# AUDIO_PR_2020.net
KiCad netlist of a schematic drawn in EAGLE
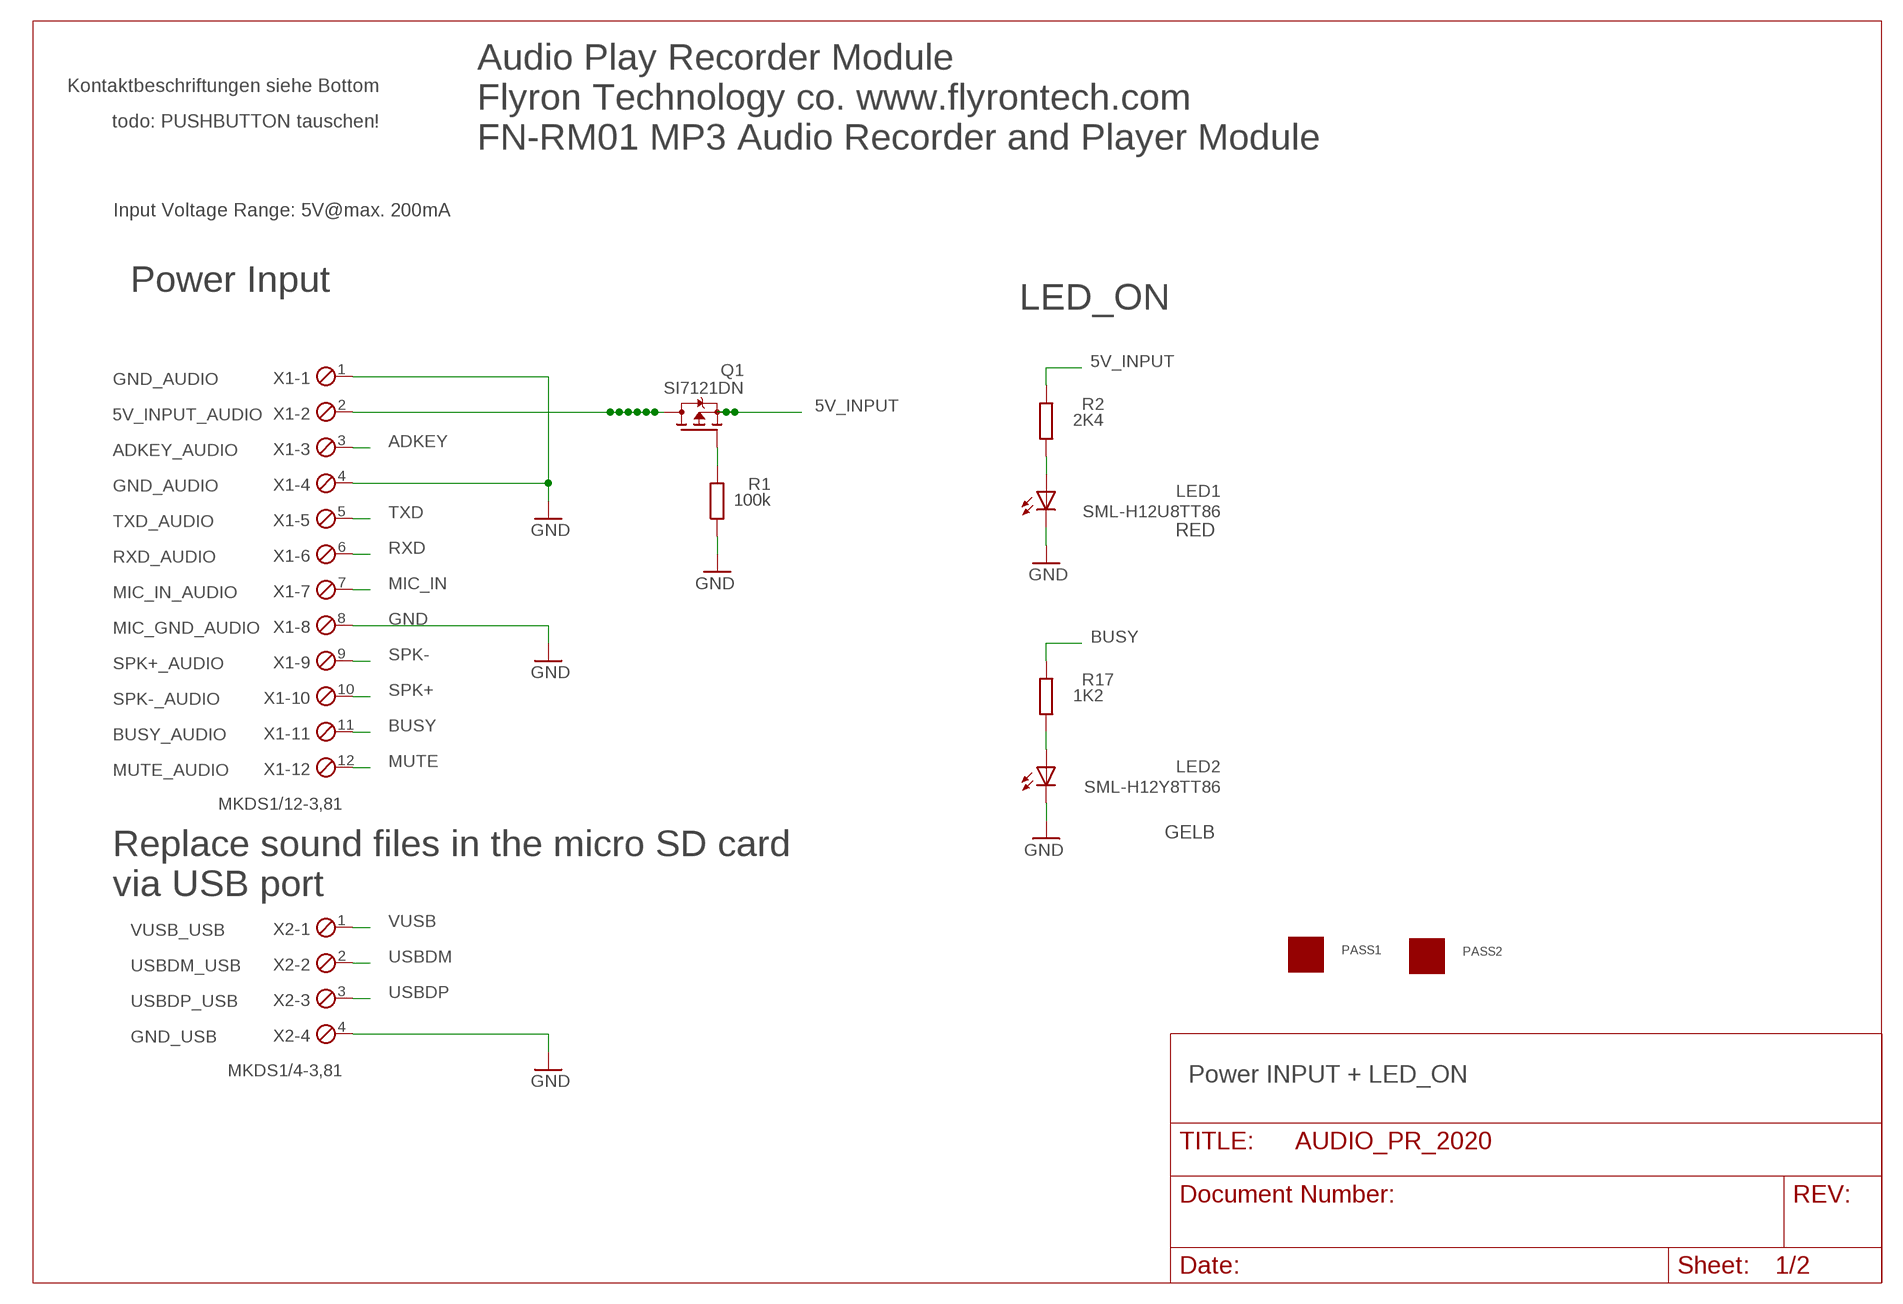
[diagram p0: schematic, sheet 1]
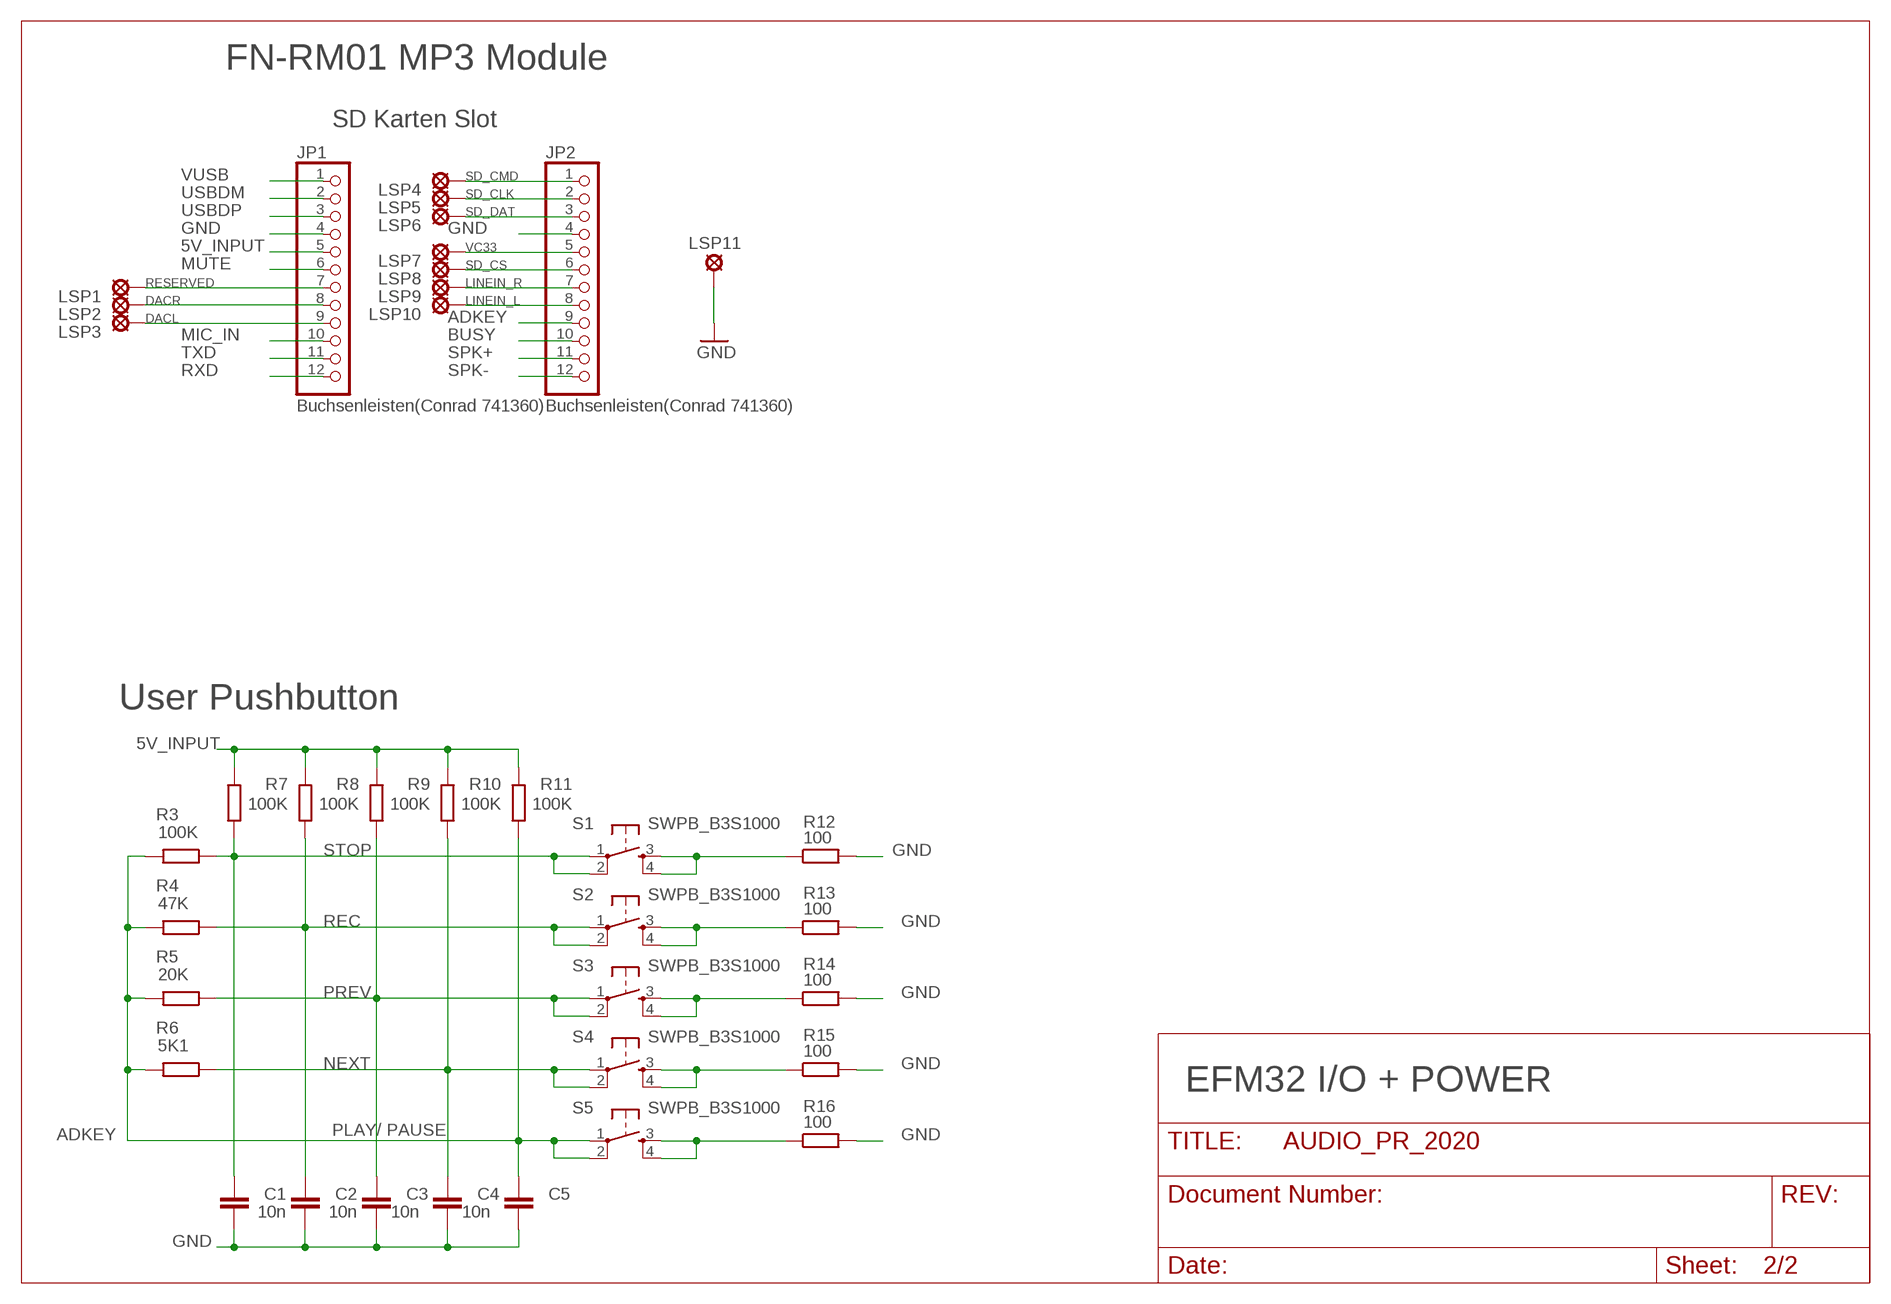
[diagram p1: schematic, sheet 2]

(export (version "E")
  (design (tool "Eeschema 10.0.6"))
  (components
    (comp (ref "LED1")
      (value "SML-H12U8TT86")
      (footprint "eagle-import:CHIPLED_0805")
      (libsource (lib "eagle-import") (part "LEDCHIPLED_0805"))
    )
    (comp (ref "LED2")
      (value "SML-H12Y8TT86")
      (footprint "eagle-import:CHIPLED_0805")
      (libsource (lib "eagle-import") (part "LEDCHIPLED_0805"))
    )
    (comp (ref "PASS1")
      (value "ROUND_1MM1.5")
      (footprint "eagle-import:ROUND2_1.5MM")
      (libsource (lib "eagle-import") (part "ROUND_1MM1.5"))
    )
    (comp (ref "PASS2")
      (value "ROUND_1MM1.5")
      (footprint "eagle-import:ROUND2_1.5MM")
      (libsource (lib "eagle-import") (part "ROUND_1MM1.5"))
    )
    (comp (ref "Q1")
      (value "SI7121DN")
      (footprint "eagle-import:TRANSISTOR-FET_1212-8S")
      (libsource (lib "eagle-import") (part "TRANSISTOR-FET_SI7113DN"))
    )
    (comp (ref "R1")
      (value "100k")
      (footprint "eagle-import:R0805")
      (libsource (lib "eagle-import") (part "R-EU_R0805"))
    )
    (comp (ref "R2")
      (value "2K4")
      (footprint "eagle-import:R0805")
      (libsource (lib "eagle-import") (part "R-EU_R0805"))
    )
    (comp (ref "R17")
      (value "1K2")
      (footprint "eagle-import:R0805")
      (libsource (lib "eagle-import") (part "R-EU_R0805"))
    )
    (comp (ref "X1")
      (value "MKDS1/12-3,81")
      (footprint "eagle-import:12POL381")
      (libsource (lib "eagle-import") (part "MKDS1/12-3,81"))
    )
    (comp (ref "X2")
      (value "MKDS1/4-3,81")
      (footprint "eagle-import:4POL381")
      (libsource (lib "eagle-import") (part "MKDS1/4-3,81"))
    )
    (comp (ref "C1")
      (value "10n")
      (footprint "eagle-import:C0603")
      (libsource (lib "eagle-import") (part "C-EUC0603"))
    )
    (comp (ref "C2")
      (value "10n")
      (footprint "eagle-import:C0603")
      (libsource (lib "eagle-import") (part "C-EUC0603"))
    )
    (comp (ref "C3")
      (value "10n")
      (footprint "eagle-import:C0603")
      (libsource (lib "eagle-import") (part "C-EUC0603"))
    )
    (comp (ref "C4")
      (value "10n")
      (footprint "eagle-import:C0603")
      (libsource (lib "eagle-import") (part "C-EUC0603"))
    )
    (comp (ref "C5")
      (value "10n")
      (footprint "eagle-import:C0603")
      (libsource (lib "eagle-import") (part "C-EUC0603"))
    )
    (comp (ref "JP1")
      (value "Buchsenleisten(Conrad 741360)")
      (footprint "eagle-import:1X12")
      (libsource (lib "eagle-import") (part "PINHD-1X12"))
    )
    (comp (ref "JP2")
      (value "Buchsenleisten(Conrad 741360)")
      (footprint "eagle-import:1X12")
      (libsource (lib "eagle-import") (part "PINHD-1X12"))
    )
    (comp (ref "LSP1")
      (value "LSP10")
      (footprint "eagle-import:LSP10")
      (libsource (lib "eagle-import") (part "LSP10"))
    )
    (comp (ref "LSP2")
      (value "LSP10")
      (footprint "eagle-import:LSP10")
      (libsource (lib "eagle-import") (part "LSP10"))
    )
    (comp (ref "LSP3")
      (value "LSP10")
      (footprint "eagle-import:LSP10")
      (libsource (lib "eagle-import") (part "LSP10"))
    )
    (comp (ref "LSP4")
      (value "LSP10")
      (footprint "eagle-import:LSP10")
      (libsource (lib "eagle-import") (part "LSP10"))
    )
    (comp (ref "LSP5")
      (value "LSP10")
      (footprint "eagle-import:LSP10")
      (libsource (lib "eagle-import") (part "LSP10"))
    )
    (comp (ref "LSP6")
      (value "LSP10")
      (footprint "eagle-import:LSP10")
      (libsource (lib "eagle-import") (part "LSP10"))
    )
    (comp (ref "LSP7")
      (value "LSP10")
      (footprint "eagle-import:LSP10")
      (libsource (lib "eagle-import") (part "LSP10"))
    )
    (comp (ref "LSP8")
      (value "LSP10")
      (footprint "eagle-import:LSP10")
      (libsource (lib "eagle-import") (part "LSP10"))
    )
    (comp (ref "LSP9")
      (value "LSP10")
      (footprint "eagle-import:LSP10")
      (libsource (lib "eagle-import") (part "LSP10"))
    )
    (comp (ref "LSP10")
      (value "LSP10")
      (footprint "eagle-import:LSP10")
      (libsource (lib "eagle-import") (part "LSP10"))
    )
    (comp (ref "LSP11")
      (value "LSP10")
      (footprint "eagle-import:LSP10")
      (libsource (lib "eagle-import") (part "LSP10"))
    )
    (comp (ref "R3")
      (value "100K")
      (footprint "eagle-import:R0805")
      (libsource (lib "eagle-import") (part "R-EU_R0805"))
    )
    (comp (ref "R4")
      (value "47K")
      (footprint "eagle-import:R0805")
      (libsource (lib "eagle-import") (part "R-EU_R0805"))
    )
    (comp (ref "R5")
      (value "20K")
      (footprint "eagle-import:R0805")
      (libsource (lib "eagle-import") (part "R-EU_R0805"))
    )
    (comp (ref "R6")
      (value "5K1")
      (footprint "eagle-import:R0805")
      (libsource (lib "eagle-import") (part "R-EU_R0805"))
    )
    (comp (ref "R7")
      (value "100K")
      (footprint "eagle-import:R0805")
      (libsource (lib "eagle-import") (part "R-EU_R0805"))
    )
    (comp (ref "R8")
      (value "100K")
      (footprint "eagle-import:R0805")
      (libsource (lib "eagle-import") (part "R-EU_R0805"))
    )
    (comp (ref "R9")
      (value "100K")
      (footprint "eagle-import:R0805")
      (libsource (lib "eagle-import") (part "R-EU_R0805"))
    )
    (comp (ref "R10")
      (value "100K")
      (footprint "eagle-import:R0805")
      (libsource (lib "eagle-import") (part "R-EU_R0805"))
    )
    (comp (ref "R11")
      (value "100K")
      (footprint "eagle-import:R0805")
      (libsource (lib "eagle-import") (part "R-EU_R0805"))
    )
    (comp (ref "R12")
      (value "100")
      (footprint "eagle-import:R0805")
      (libsource (lib "eagle-import") (part "R-EU_R0805"))
    )
    (comp (ref "R13")
      (value "100")
      (footprint "eagle-import:R0805")
      (libsource (lib "eagle-import") (part "R-EU_R0805"))
    )
    (comp (ref "R14")
      (value "100")
      (footprint "eagle-import:R0805")
      (libsource (lib "eagle-import") (part "R-EU_R0805"))
    )
    (comp (ref "R15")
      (value "100")
      (footprint "eagle-import:R0805")
      (libsource (lib "eagle-import") (part "R-EU_R0805"))
    )
    (comp (ref "R16")
      (value "100")
      (footprint "eagle-import:R0805")
      (libsource (lib "eagle-import") (part "R-EU_R0805"))
    )
    (comp (ref "S1")
      (value "SWPB_B3S1000")
      (footprint "eagle-import:DTSM-6")
      (libsource (lib "eagle-import") (part "DTSM-6"))
    )
    (comp (ref "S2")
      (value "SWPB_B3S1000")
      (footprint "eagle-import:DTSM-6")
      (libsource (lib "eagle-import") (part "DTSM-6"))
    )
    (comp (ref "S3")
      (value "SWPB_B3S1000")
      (footprint "eagle-import:DTSM-6")
      (libsource (lib "eagle-import") (part "DTSM-6"))
    )
    (comp (ref "S4")
      (value "SWPB_B3S1000")
      (footprint "eagle-import:DTSM-6")
      (libsource (lib "eagle-import") (part "DTSM-6"))
    )
    (comp (ref "S5")
      (value "SWPB_B3S1000")
      (footprint "eagle-import:DTSM-6")
      (libsource (lib "eagle-import") (part "DTSM-6"))
    )
  )
  (nets
    (net (code "1") (name "5V_INPUT") (class "Default")
      (node (ref "JP1") (pin "5") (pinfunction "5_5") (pintype "passive"))
      (node (ref "Q1") (pin "1") (pinfunction "S_1") (pintype "passive"))
      (node (ref "Q1") (pin "2") (pinfunction "S_2") (pintype "passive"))
      (node (ref "Q1") (pin "3") (pinfunction "S_3") (pintype "passive"))
      (node (ref "R10") (pin "2") (pinfunction "2_2") (pintype "passive"))
      (node (ref "R11") (pin "2") (pinfunction "2_2") (pintype "passive"))
      (node (ref "R2") (pin "1") (pinfunction "1_1") (pintype "passive"))
      (node (ref "R7") (pin "2") (pinfunction "2_2") (pintype "passive"))
      (node (ref "R8") (pin "2") (pinfunction "2_2") (pintype "passive"))
      (node (ref "R9") (pin "2") (pinfunction "2_2") (pintype "passive"))
    )
    (net (code "2") (name "ADKEY") (class "Default")
      (node (ref "C5") (pin "2") (pinfunction "2_2") (pintype "passive"))
      (node (ref "JP2") (pin "9") (pinfunction "9_9") (pintype "passive"))
      (node (ref "R11") (pin "1") (pinfunction "1_1") (pintype "passive"))
      (node (ref "R3") (pin "2") (pinfunction "2_2") (pintype "passive"))
      (node (ref "R4") (pin "2") (pinfunction "2_2") (pintype "passive"))
      (node (ref "R5") (pin "2") (pinfunction "2_2") (pintype "passive"))
      (node (ref "R6") (pin "2") (pinfunction "2_2") (pintype "passive"))
      (node (ref "S5") (pin "1") (pinfunction "1_1") (pintype "passive"))
      (node (ref "S5") (pin "2") (pinfunction "2_2") (pintype "passive"))
      (node (ref "X1") (pin "3") (pinfunction "1_3") (pintype "passive"))
    )
    (net (code "3") (name "BUSY") (class "Default")
      (node (ref "JP2") (pin "10") (pinfunction "10_10") (pintype "passive"))
      (node (ref "R17") (pin "1") (pinfunction "1_1") (pintype "passive"))
      (node (ref "X1") (pin "11") (pinfunction "1_11") (pintype "passive"))
    )
    (net (code "4") (name "DACL") (class "Default")
      (node (ref "JP1") (pin "9") (pinfunction "9_9") (pintype "passive"))
      (node (ref "LSP3") (pin "MP") (pinfunction "MP_MP") (pintype "passive"))
    )
    (net (code "5") (name "DACR") (class "Default")
      (node (ref "JP1") (pin "8") (pinfunction "8_8") (pintype "passive"))
      (node (ref "LSP2") (pin "MP") (pinfunction "MP_MP") (pintype "passive"))
    )
    (net (code "6") (name "GND") (class "Default")
      (node (ref "C1") (pin "1") (pinfunction "1_1") (pintype "passive"))
      (node (ref "C2") (pin "1") (pinfunction "1_1") (pintype "passive"))
      (node (ref "C3") (pin "1") (pinfunction "1_1") (pintype "passive"))
      (node (ref "C4") (pin "1") (pinfunction "1_1") (pintype "passive"))
      (node (ref "C5") (pin "1") (pinfunction "1_1") (pintype "passive"))
      (node (ref "JP1") (pin "4") (pinfunction "4_4") (pintype "passive"))
      (node (ref "JP2") (pin "4") (pinfunction "4_4") (pintype "passive"))
      (node (ref "LED1") (pin "C") (pinfunction "C_C") (pintype "passive"))
      (node (ref "LED2") (pin "C") (pinfunction "C_C") (pintype "passive"))
      (node (ref "LSP11") (pin "MP") (pinfunction "MP_MP") (pintype "passive"))
      (node (ref "R1") (pin "1") (pinfunction "1_1") (pintype "passive"))
      (node (ref "R12") (pin "2") (pinfunction "2_2") (pintype "passive"))
      (node (ref "R13") (pin "2") (pinfunction "2_2") (pintype "passive"))
      (node (ref "R14") (pin "2") (pinfunction "2_2") (pintype "passive"))
      (node (ref "R15") (pin "2") (pinfunction "2_2") (pintype "passive"))
      (node (ref "R16") (pin "2") (pinfunction "2_2") (pintype "passive"))
      (node (ref "X1") (pin "1") (pinfunction "1_1") (pintype "passive"))
      (node (ref "X1") (pin "4") (pinfunction "1_4") (pintype "passive"))
      (node (ref "X1") (pin "8") (pinfunction "1_8") (pintype "passive"))
      (node (ref "X2") (pin "4") (pinfunction "1_4") (pintype "passive"))
    )
    (net (code "7") (name "LINEIN_L") (class "Default")
      (node (ref "JP2") (pin "8") (pinfunction "8_8") (pintype "passive"))
      (node (ref "LSP10") (pin "MP") (pinfunction "MP_MP") (pintype "passive"))
    )
    (net (code "8") (name "LINEIN_R") (class "Default")
      (node (ref "JP2") (pin "7") (pinfunction "7_7") (pintype "passive"))
      (node (ref "LSP9") (pin "MP") (pinfunction "MP_MP") (pintype "passive"))
    )
    (net (code "9") (name "MIC_IN") (class "Default")
      (node (ref "JP1") (pin "10") (pinfunction "10_10") (pintype "passive"))
      (node (ref "X1") (pin "7") (pinfunction "1_7") (pintype "passive"))
    )
    (net (code "10") (name "MUTE") (class "Default")
      (node (ref "JP1") (pin "6") (pinfunction "6_6") (pintype "passive"))
      (node (ref "X1") (pin "12") (pinfunction "1_12") (pintype "passive"))
    )
    (net (code "11") (name "NEXT") (class "Default")
      (node (ref "C4") (pin "2") (pinfunction "2_2") (pintype "passive"))
      (node (ref "R10") (pin "1") (pinfunction "1_1") (pintype "passive"))
      (node (ref "R6") (pin "1") (pinfunction "1_1") (pintype "passive"))
      (node (ref "S4") (pin "1") (pinfunction "1_1") (pintype "passive"))
      (node (ref "S4") (pin "2") (pinfunction "2_2") (pintype "passive"))
    )
    (net (code "12") (name "Net-(LED1-PadA)") (class "Default")
      (node (ref "LED1") (pin "A") (pinfunction "A_A") (pintype "passive"))
      (node (ref "R2") (pin "2") (pinfunction "2_2") (pintype "passive"))
    )
    (net (code "13") (name "Net-(LED2-PadA)") (class "Default")
      (node (ref "LED2") (pin "A") (pinfunction "A_A") (pintype "passive"))
      (node (ref "R17") (pin "2") (pinfunction "2_2") (pintype "passive"))
    )
    (net (code "14") (name "Net-(Q1-G)") (class "Default")
      (node (ref "Q1") (pin "4") (pinfunction "G_4") (pintype "passive"))
      (node (ref "R1") (pin "2") (pinfunction "2_2") (pintype "passive"))
    )
    (net (code "15") (name "Net-(R12-Pad1)") (class "Default")
      (node (ref "R12") (pin "1") (pinfunction "1_1") (pintype "passive"))
      (node (ref "S1") (pin "3") (pinfunction "3_3") (pintype "passive"))
      (node (ref "S1") (pin "4") (pinfunction "4_4") (pintype "passive"))
    )
    (net (code "16") (name "Net-(R13-Pad1)") (class "Default")
      (node (ref "R13") (pin "1") (pinfunction "1_1") (pintype "passive"))
      (node (ref "S2") (pin "3") (pinfunction "3_3") (pintype "passive"))
      (node (ref "S2") (pin "4") (pinfunction "4_4") (pintype "passive"))
    )
    (net (code "17") (name "Net-(R14-Pad1)") (class "Default")
      (node (ref "R14") (pin "1") (pinfunction "1_1") (pintype "passive"))
      (node (ref "S3") (pin "3") (pinfunction "3_3") (pintype "passive"))
      (node (ref "S3") (pin "4") (pinfunction "4_4") (pintype "passive"))
    )
    (net (code "18") (name "Net-(R15-Pad1)") (class "Default")
      (node (ref "R15") (pin "1") (pinfunction "1_1") (pintype "passive"))
      (node (ref "S4") (pin "3") (pinfunction "3_3") (pintype "passive"))
      (node (ref "S4") (pin "4") (pinfunction "4_4") (pintype "passive"))
    )
    (net (code "19") (name "Net-(R16-Pad1)") (class "Default")
      (node (ref "R16") (pin "1") (pinfunction "1_1") (pintype "passive"))
      (node (ref "S5") (pin "3") (pinfunction "3_3") (pintype "passive"))
      (node (ref "S5") (pin "4") (pinfunction "4_4") (pintype "passive"))
    )
    (net (code "20") (name "Net-(X1E-1)") (class "Default")
      (node (ref "Q1") (pin "10") (pinfunction "D_10") (pintype "passive"))
      (node (ref "Q1") (pin "11") (pinfunction "D_11") (pintype "passive"))
      (node (ref "Q1") (pin "5") (pinfunction "D_5") (pintype "passive"))
      (node (ref "Q1") (pin "6") (pinfunction "D_6") (pintype "passive"))
      (node (ref "Q1") (pin "7") (pinfunction "D_7") (pintype "passive"))
      (node (ref "Q1") (pin "8") (pinfunction "D_8") (pintype "passive"))
      (node (ref "Q1") (pin "9") (pinfunction "D_9") (pintype "passive"))
      (node (ref "X1") (pin "2") (pinfunction "1_2") (pintype "passive"))
    )
    (net (code "21") (name "PREV") (class "Default")
      (node (ref "C3") (pin "2") (pinfunction "2_2") (pintype "passive"))
      (node (ref "R5") (pin "1") (pinfunction "1_1") (pintype "passive"))
      (node (ref "R9") (pin "1") (pinfunction "1_1") (pintype "passive"))
      (node (ref "S3") (pin "1") (pinfunction "1_1") (pintype "passive"))
      (node (ref "S3") (pin "2") (pinfunction "2_2") (pintype "passive"))
    )
    (net (code "22") (name "REC") (class "Default")
      (node (ref "C2") (pin "2") (pinfunction "2_2") (pintype "passive"))
      (node (ref "R4") (pin "1") (pinfunction "1_1") (pintype "passive"))
      (node (ref "R8") (pin "1") (pinfunction "1_1") (pintype "passive"))
      (node (ref "S2") (pin "1") (pinfunction "1_1") (pintype "passive"))
      (node (ref "S2") (pin "2") (pinfunction "2_2") (pintype "passive"))
    )
    (net (code "23") (name "RESERVED") (class "Default")
      (node (ref "JP1") (pin "7") (pinfunction "7_7") (pintype "passive"))
      (node (ref "LSP1") (pin "MP") (pinfunction "MP_MP") (pintype "passive"))
    )
    (net (code "24") (name "RXD") (class "Default")
      (node (ref "JP1") (pin "12") (pinfunction "12_12") (pintype "passive"))
      (node (ref "X1") (pin "6") (pinfunction "1_6") (pintype "passive"))
    )
    (net (code "25") (name "SD_CLK") (class "Default")
      (node (ref "JP2") (pin "2") (pinfunction "2_2") (pintype "passive"))
      (node (ref "LSP5") (pin "MP") (pinfunction "MP_MP") (pintype "passive"))
    )
    (net (code "26") (name "SD_CMD") (class "Default")
      (node (ref "JP2") (pin "1") (pinfunction "1_1") (pintype "passive"))
      (node (ref "LSP4") (pin "MP") (pinfunction "MP_MP") (pintype "passive"))
    )
    (net (code "27") (name "SD_CS") (class "Default")
      (node (ref "JP2") (pin "6") (pinfunction "6_6") (pintype "passive"))
      (node (ref "LSP8") (pin "MP") (pinfunction "MP_MP") (pintype "passive"))
    )
    (net (code "28") (name "SD_DAT") (class "Default")
      (node (ref "JP2") (pin "3") (pinfunction "3_3") (pintype "passive"))
      (node (ref "LSP6") (pin "MP") (pinfunction "MP_MP") (pintype "passive"))
    )
    (net (code "29") (name "SPK+") (class "Default")
      (node (ref "JP2") (pin "11") (pinfunction "11_11") (pintype "passive"))
      (node (ref "X1") (pin "10") (pinfunction "1_10") (pintype "passive"))
    )
    (net (code "30") (name "SPK-") (class "Default")
      (node (ref "JP2") (pin "12") (pinfunction "12_12") (pintype "passive"))
      (node (ref "X1") (pin "9") (pinfunction "1_9") (pintype "passive"))
    )
    (net (code "31") (name "STOP") (class "Default")
      (node (ref "C1") (pin "2") (pinfunction "2_2") (pintype "passive"))
      (node (ref "R3") (pin "1") (pinfunction "1_1") (pintype "passive"))
      (node (ref "R7") (pin "1") (pinfunction "1_1") (pintype "passive"))
      (node (ref "S1") (pin "1") (pinfunction "1_1") (pintype "passive"))
      (node (ref "S1") (pin "2") (pinfunction "2_2") (pintype "passive"))
    )
    (net (code "32") (name "TXD") (class "Default")
      (node (ref "JP1") (pin "11") (pinfunction "11_11") (pintype "passive"))
      (node (ref "X1") (pin "5") (pinfunction "1_5") (pintype "passive"))
    )
    (net (code "33") (name "USBDM") (class "Default")
      (node (ref "JP1") (pin "2") (pinfunction "2_2") (pintype "passive"))
      (node (ref "X2") (pin "2") (pinfunction "1_2") (pintype "passive"))
    )
    (net (code "34") (name "USBDP") (class "Default")
      (node (ref "JP1") (pin "3") (pinfunction "3_3") (pintype "passive"))
      (node (ref "X2") (pin "3") (pinfunction "1_3") (pintype "passive"))
    )
    (net (code "35") (name "VC33") (class "Default")
      (node (ref "JP2") (pin "5") (pinfunction "5_5") (pintype "passive"))
      (node (ref "LSP7") (pin "MP") (pinfunction "MP_MP") (pintype "passive"))
    )
    (net (code "36") (name "VUSB") (class "Default")
      (node (ref "JP1") (pin "1") (pinfunction "1_1") (pintype "passive"))
      (node (ref "X2") (pin "1") (pinfunction "1_1") (pintype "passive"))
    )
  )
)
